# Sintetizador-AD9102_V03_R00.net
KiCad netlist of a schematic drawn in Altium Designer
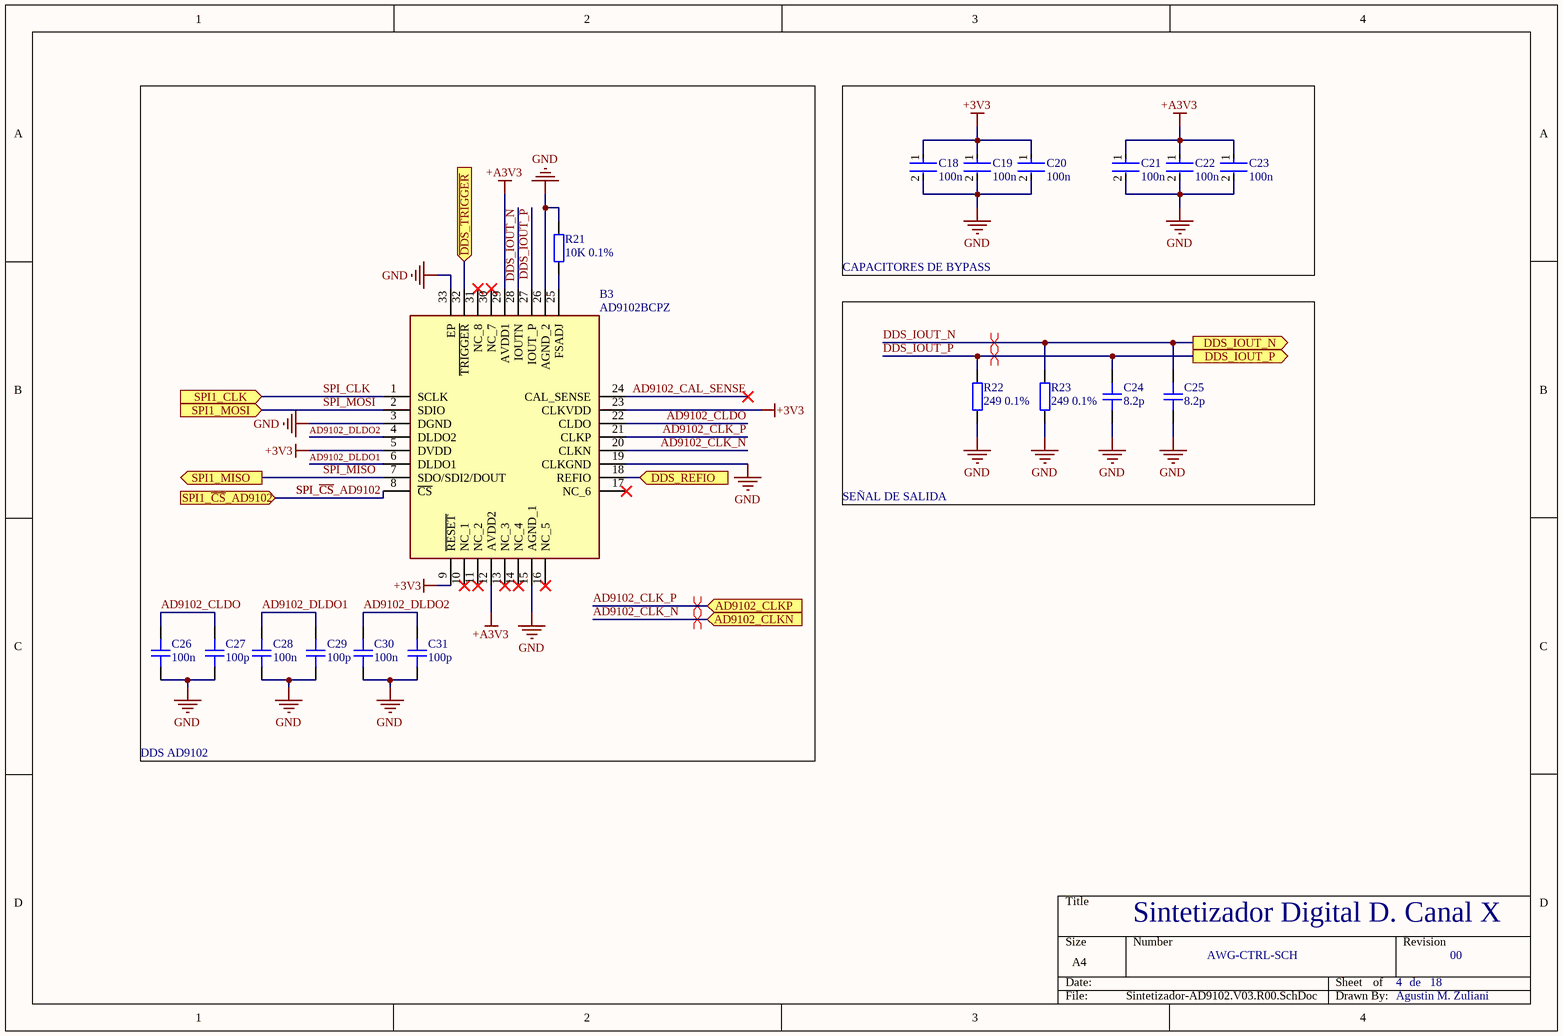
[diagram p0: Sintetizador-AD9102.V03.R00.SchDoc]

(export (version "E")
  (design (tool "Eeschema 10.0.6"))
  (components
    (comp (ref "B3")
      (value "AD9102BCPZ")
      (footprint "QFN50P500X500X80-33N-D")
      (description "Analog Devices AD9102BCPZ, 14 bit Serial DAC, 180Msps, 32-Pin LFCSP")
      (fields (field (name "MOUSER PART NUMBER") "584-AD9102BCPZ"))
      (libsource (lib "AD9102BCPZ") (part "AD9102BCPZ"))
    )
    (comp (ref "C18")
      (value "100n")
      (footprint "FP-CC0805-EB-MFG")
      (description "CC0805KKX7RYBB104 Capacitor Ceramic 0.01uF 250V X7R 10% 0805 T/R")
      (fields (field (name "TOLERANCE") "10%"))
      (libsource (lib "Altium Content Vault") (part "b4654b650e69147ec39a6b967a45e02"))
    )
    (comp (ref "C19")
      (value "100n")
      (footprint "FP-CC0805-EB-MFG")
      (description "CC0805KKX7RYBB104 Capacitor Ceramic 0.01uF 250V X7R 10% 0805 T/R")
      (fields (field (name "TOLERANCE") "10%"))
      (libsource (lib "Altium Content Vault") (part "b4654b650e69147ec39a6b967a45e02"))
    )
    (comp (ref "C20")
      (value "100n")
      (footprint "FP-CC0805-EB-MFG")
      (description "CC0805KKX7RYBB104 Capacitor Ceramic 0.01uF 250V X7R 10% 0805 T/R")
      (fields (field (name "TOLERANCE") "10%"))
      (libsource (lib "Altium Content Vault") (part "b4654b650e69147ec39a6b967a45e02"))
    )
    (comp (ref "C21")
      (value "100n")
      (footprint "FP-CC0805-EB-MFG")
      (description "CC0805KKX7RYBB104 Capacitor Ceramic 0.01uF 250V X7R 10% 0805 T/R")
      (fields (field (name "TOLERANCE") "10%"))
      (libsource (lib "Altium Content Vault") (part "b4654b650e69147ec39a6b967a45e02"))
    )
    (comp (ref "C22")
      (value "100n")
      (footprint "FP-CC0805-EB-MFG")
      (description "CC0805KKX7RYBB104 Capacitor Ceramic 0.01uF 250V X7R 10% 0805 T/R")
      (fields (field (name "TOLERANCE") "10%"))
      (libsource (lib "Altium Content Vault") (part "b4654b650e69147ec39a6b967a45e02"))
    )
    (comp (ref "C23")
      (value "100n")
      (footprint "FP-CC0805-EB-MFG")
      (description "CC0805KKX7RYBB104 Capacitor Ceramic 0.01uF 250V X7R 10% 0805 T/R")
      (fields (field (name "TOLERANCE") "10%"))
      (libsource (lib "Altium Content Vault") (part "b4654b650e69147ec39a6b967a45e02"))
    )
    (comp (ref "C24")
      (value "8.2p")
      (footprint "CAP_0805")
      (description "Capacitor SMD 0805")
      (libsource (lib "Schematic-Lib-PhilsLab") (part "CAP_0805"))
    )
    (comp (ref "C25")
      (value "8.2p")
      (footprint "CAP_0805")
      (description "Capacitor SMD 0805")
      (libsource (lib "Schematic-Lib-PhilsLab") (part "CAP_0805"))
    )
    (comp (ref "C26")
      (value "100n")
      (footprint "CAP_0805")
      (description "Capacitor SMD 0805")
      (libsource (lib "Schematic-Lib-PhilsLab") (part "CAP_0805"))
    )
    (comp (ref "C27")
      (value "100p")
      (footprint "CAP_0805")
      (description "Capacitor SMD 0805")
      (libsource (lib "Schematic-Lib-PhilsLab") (part "CAP_0805"))
    )
    (comp (ref "C28")
      (value "100n")
      (footprint "CAP_0805")
      (description "Capacitor SMD 0805")
      (libsource (lib "Schematic-Lib-PhilsLab") (part "CAP_0805"))
    )
    (comp (ref "C29")
      (value "100p")
      (footprint "CAP_0805")
      (description "Capacitor SMD 0805")
      (libsource (lib "Schematic-Lib-PhilsLab") (part "CAP_0805"))
    )
    (comp (ref "C30")
      (value "100n")
      (footprint "CAP_0805")
      (description "Capacitor SMD 0805")
      (libsource (lib "Schematic-Lib-PhilsLab") (part "CAP_0805"))
    )
    (comp (ref "C31")
      (value "100p")
      (footprint "CAP_0805")
      (description "Capacitor SMD 0805")
      (libsource (lib "Schematic-Lib-PhilsLab") (part "CAP_0805"))
    )
    (comp (ref "R21")
      (value "10K 0.1%")
      (footprint "RES_0805")
      (description "Resistor SMD 0805")
      (libsource (lib "Schematic-Lib-PhilsLab") (part "RES_0805"))
    )
    (comp (ref "R22")
      (value "249 0.1%")
      (footprint "RES_0805")
      (description "Resistor SMD 0805")
      (libsource (lib "Schematic-Lib-PhilsLab") (part "RES_0805"))
    )
    (comp (ref "R23")
      (value "249 0.1%")
      (footprint "RES_0805")
      (description "Resistor SMD 0805")
      (libsource (lib "Schematic-Lib-PhilsLab") (part "RES_0805"))
    )
  )
  (nets
    (net (code "1") (name "+3V3") (class "Default")
      (node (ref "B3") (pin "23") (pinfunction "CLKVDD_23") (pintype "passive"))
      (node (ref "B3") (pin "5") (pinfunction "DVDD_5") (pintype "passive"))
      (node (ref "B3") (pin "9") (pinfunction "~{RESET}_9") (pintype "passive"))
      (node (ref "C18") (pin "1") (pinfunction "1_1") (pintype "passive"))
      (node (ref "C19") (pin "1") (pinfunction "1_1") (pintype "passive"))
      (node (ref "C20") (pin "1") (pinfunction "1_1") (pintype "passive"))
    )
    (net (code "2") (name "+A3V3") (class "Default")
      (node (ref "B3") (pin "12") (pinfunction "AVDD2_12") (pintype "passive"))
      (node (ref "B3") (pin "29") (pinfunction "AVDD1_29") (pintype "passive"))
      (node (ref "C21") (pin "1") (pinfunction "1_1") (pintype "passive"))
      (node (ref "C22") (pin "1") (pinfunction "1_1") (pintype "passive"))
      (node (ref "C23") (pin "1") (pinfunction "1_1") (pintype "passive"))
    )
    (net (code "3") (name "/AD9102_CAL_SENSE") (class "Default")
      (node (ref "B3") (pin "24") (pinfunction "CAL_SENSE_24") (pintype "passive+no_connect"))
    )
    (net (code "4") (name "/AD9102_CLDO") (class "Default")
      (node (ref "B3") (pin "22") (pinfunction "CLDO_22") (pintype "passive"))
      (node (ref "C26") (pin "2") (pinfunction "2_2") (pintype "passive"))
      (node (ref "C27") (pin "2") (pinfunction "2_2") (pintype "passive"))
    )
    (net (code "5") (name "/AD9102_CLK_N") (class "Default")
      (node (ref "B3") (pin "20") (pinfunction "CLKN_20") (pintype "passive"))
    )
    (net (code "6") (name "/AD9102_CLK_P") (class "Default")
      (node (ref "B3") (pin "21") (pinfunction "CLKP_21") (pintype "passive"))
    )
    (net (code "7") (name "/AD9102_DLDO1") (class "Default")
      (node (ref "B3") (pin "6") (pinfunction "DLDO1_6") (pintype "passive"))
      (node (ref "C28") (pin "2") (pinfunction "2_2") (pintype "passive"))
      (node (ref "C29") (pin "2") (pinfunction "2_2") (pintype "passive"))
    )
    (net (code "8") (name "/AD9102_DLDO2") (class "Default")
      (node (ref "B3") (pin "4") (pinfunction "DLDO2_4") (pintype "passive"))
      (node (ref "C30") (pin "2") (pinfunction "2_2") (pintype "passive"))
      (node (ref "C31") (pin "2") (pinfunction "2_2") (pintype "passive"))
    )
    (net (code "9") (name "/DDS_IOUT_N") (class "Default")
      (node (ref "B3") (pin "28") (pinfunction "IOUTN_28") (pintype "passive"))
      (node (ref "C25") (pin "1") (pinfunction "1_1") (pintype "passive"))
      (node (ref "R23") (pin "2") (pinfunction "2_2") (pintype "passive"))
    )
    (net (code "10") (name "/DDS_IOUT_P") (class "Default")
      (node (ref "B3") (pin "27") (pinfunction "IOUT_P_27") (pintype "passive"))
      (node (ref "C24") (pin "1") (pinfunction "1_1") (pintype "passive"))
      (node (ref "R22") (pin "2") (pinfunction "2_2") (pintype "passive"))
    )
    (net (code "11") (name "/DDS_REFIO") (class "Default")
      (node (ref "B3") (pin "18") (pinfunction "REFIO_18") (pintype "passive"))
    )
    (net (code "12") (name "/DDS_TRIGGER") (class "Default")
      (node (ref "B3") (pin "32") (pinfunction "~{TRIGGER}_32") (pintype "passive"))
    )
    (net (code "13") (name "/SPI_CLK") (class "Default")
      (node (ref "B3") (pin "1") (pinfunction "SCLK_1") (pintype "passive"))
    )
    (net (code "14") (name "/SPI_MISO") (class "Default")
      (node (ref "B3") (pin "7") (pinfunction "SDO/SDI2/DOUT_7") (pintype "passive"))
    )
    (net (code "15") (name "/SPI_MOSI") (class "Default")
      (node (ref "B3") (pin "2") (pinfunction "SDIO_2") (pintype "passive"))
    )
    (net (code "16") (name "/SPI_~{CS}") (class "Default")
      (node (ref "B3") (pin "8") (pinfunction "~{CS}_8") (pintype "passive"))
    )
    (net (code "17") (name "GND") (class "Default")
      (node (ref "B3") (pin "15") (pinfunction "AGND_1_15") (pintype "passive"))
      (node (ref "B3") (pin "19") (pinfunction "CLKGND_19") (pintype "passive"))
      (node (ref "B3") (pin "26") (pinfunction "AGND_2_26") (pintype "passive"))
      (node (ref "B3") (pin "3") (pinfunction "DGND_3") (pintype "passive"))
      (node (ref "B3") (pin "33") (pinfunction "EP_33") (pintype "passive"))
      (node (ref "C18") (pin "2") (pinfunction "2_2") (pintype "passive"))
      (node (ref "C19") (pin "2") (pinfunction "2_2") (pintype "passive"))
      (node (ref "C20") (pin "2") (pinfunction "2_2") (pintype "passive"))
      (node (ref "C21") (pin "2") (pinfunction "2_2") (pintype "passive"))
      (node (ref "C22") (pin "2") (pinfunction "2_2") (pintype "passive"))
      (node (ref "C23") (pin "2") (pinfunction "2_2") (pintype "passive"))
      (node (ref "C24") (pin "2") (pinfunction "2_2") (pintype "passive"))
      (node (ref "C25") (pin "2") (pinfunction "2_2") (pintype "passive"))
      (node (ref "C26") (pin "1") (pinfunction "1_1") (pintype "passive"))
      (node (ref "C27") (pin "1") (pinfunction "1_1") (pintype "passive"))
      (node (ref "C28") (pin "1") (pinfunction "1_1") (pintype "passive"))
      (node (ref "C29") (pin "1") (pinfunction "1_1") (pintype "passive"))
      (node (ref "C30") (pin "1") (pinfunction "1_1") (pintype "passive"))
      (node (ref "C31") (pin "1") (pinfunction "1_1") (pintype "passive"))
      (node (ref "R21") (pin "2") (pinfunction "2_2") (pintype "passive"))
      (node (ref "R22") (pin "1") (pinfunction "1_1") (pintype "passive"))
      (node (ref "R23") (pin "1") (pinfunction "1_1") (pintype "passive"))
    )
    (net (code "18") (name "Net-(B3-FSADJ)") (class "Default")
      (node (ref "B3") (pin "25") (pinfunction "FSADJ_25") (pintype "passive"))
      (node (ref "R21") (pin "1") (pinfunction "1_1") (pintype "passive"))
    )
    (net (code "19") (name "unconnected-(B3-NC_1-Pad10)") (class "Default")
      (node (ref "B3") (pin "10") (pinfunction "NC_1_10") (pintype "passive+no_connect"))
    )
    (net (code "20") (name "unconnected-(B3-NC_2-Pad11)") (class "Default")
      (node (ref "B3") (pin "11") (pinfunction "NC_2_11") (pintype "passive+no_connect"))
    )
    (net (code "21") (name "unconnected-(B3-NC_3-Pad13)") (class "Default")
      (node (ref "B3") (pin "13") (pinfunction "NC_3_13") (pintype "passive+no_connect"))
    )
    (net (code "22") (name "unconnected-(B3-NC_4-Pad14)") (class "Default")
      (node (ref "B3") (pin "14") (pinfunction "NC_4_14") (pintype "passive+no_connect"))
    )
    (net (code "23") (name "unconnected-(B3-NC_5-Pad16)") (class "Default")
      (node (ref "B3") (pin "16") (pinfunction "NC_5_16") (pintype "passive+no_connect"))
    )
    (net (code "24") (name "unconnected-(B3-NC_6-Pad17)") (class "Default")
      (node (ref "B3") (pin "17") (pinfunction "NC_6_17") (pintype "passive+no_connect"))
    )
    (net (code "25") (name "unconnected-(B3-NC_7-Pad30)") (class "Default")
      (node (ref "B3") (pin "30") (pinfunction "NC_7_30") (pintype "passive+no_connect"))
    )
    (net (code "26") (name "unconnected-(B3-NC_8-Pad31)") (class "Default")
      (node (ref "B3") (pin "31") (pinfunction "NC_8_31") (pintype "passive+no_connect"))
    )
  )
)
